# SOC_2_0.net
KiCad netlist of a schematic drawn in EAGLE
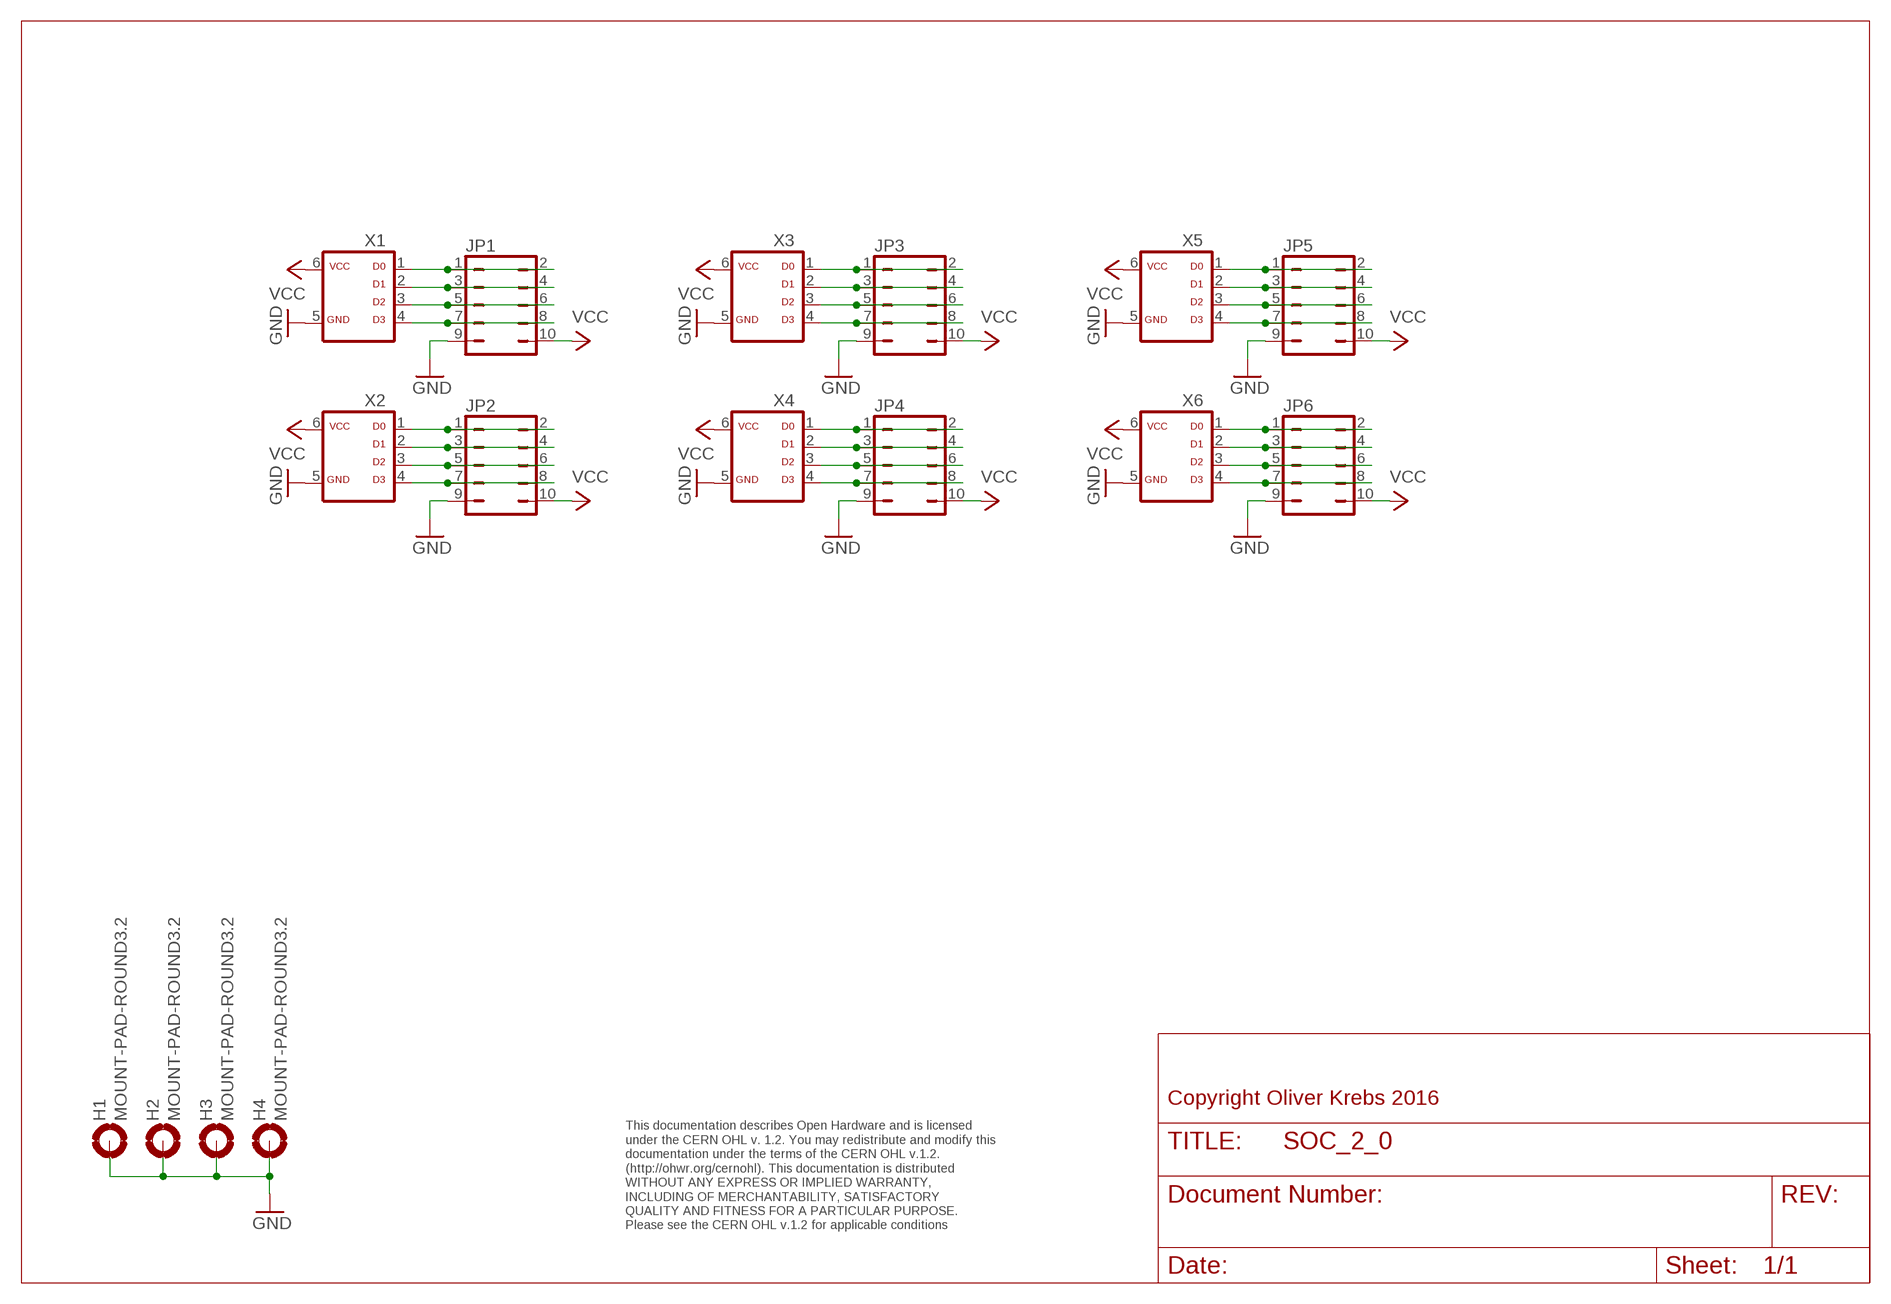
[diagram p0: schematic, sheet 1]

(export (version "E")
  (design (tool "Eeschema 10.0.6"))
  (components
    (comp (ref "H1")
      (value "MOUNT-PAD-ROUND3.2")
      (footprint "eagle-import:3,2-PAD")
      (libsource (lib "eagle-import") (part "MOUNT-PAD-ROUND3.2"))
    )
    (comp (ref "H2")
      (value "MOUNT-PAD-ROUND3.2")
      (footprint "eagle-import:3,2-PAD")
      (libsource (lib "eagle-import") (part "MOUNT-PAD-ROUND3.2"))
    )
    (comp (ref "H3")
      (value "MOUNT-PAD-ROUND3.2")
      (footprint "eagle-import:3,2-PAD")
      (libsource (lib "eagle-import") (part "MOUNT-PAD-ROUND3.2"))
    )
    (comp (ref "H4")
      (value "MOUNT-PAD-ROUND3.2")
      (footprint "eagle-import:3,2-PAD")
      (libsource (lib "eagle-import") (part "MOUNT-PAD-ROUND3.2"))
    )
    (comp (ref "JP1")
      (value "JP5Q")
      (footprint "eagle-import:JP5Q")
      (libsource (lib "eagle-import") (part "JP5Q"))
    )
    (comp (ref "JP2")
      (value "JP5Q")
      (footprint "eagle-import:JP5Q")
      (libsource (lib "eagle-import") (part "JP5Q"))
    )
    (comp (ref "JP3")
      (value "JP5Q")
      (footprint "eagle-import:JP5Q")
      (libsource (lib "eagle-import") (part "JP5Q"))
    )
    (comp (ref "JP4")
      (value "JP5Q")
      (footprint "eagle-import:JP5Q")
      (libsource (lib "eagle-import") (part "JP5Q"))
    )
    (comp (ref "JP5")
      (value "JP5Q")
      (footprint "eagle-import:JP5Q")
      (libsource (lib "eagle-import") (part "JP5Q"))
    )
    (comp (ref "JP6")
      (value "JP5Q")
      (footprint "eagle-import:JP5Q")
      (libsource (lib "eagle-import") (part "JP5Q"))
    )
    (comp (ref "X1")
      (value "ML6D")
      (footprint "eagle-import:ML-6")
      (libsource (lib "eagle-import") (part "ML6D"))
    )
    (comp (ref "X2")
      (value "ML6D")
      (footprint "eagle-import:ML-6")
      (libsource (lib "eagle-import") (part "ML6D"))
    )
    (comp (ref "X3")
      (value "ML6D")
      (footprint "eagle-import:ML-6")
      (libsource (lib "eagle-import") (part "ML6D"))
    )
    (comp (ref "X4")
      (value "ML6D")
      (footprint "eagle-import:ML-6")
      (libsource (lib "eagle-import") (part "ML6D"))
    )
    (comp (ref "X5")
      (value "ML6D")
      (footprint "eagle-import:ML-6")
      (libsource (lib "eagle-import") (part "ML6D"))
    )
    (comp (ref "X6")
      (value "ML6D")
      (footprint "eagle-import:ML-6")
      (libsource (lib "eagle-import") (part "ML6D"))
    )
  )
  (nets
    (net (code "1") (name "GND") (class "Default")
      (node (ref "H1") (pin "B3,2") (pinfunction "MOUNT_B3,2") (pintype "passive"))
      (node (ref "H2") (pin "B3,2") (pinfunction "MOUNT_B3,2") (pintype "passive"))
      (node (ref "H3") (pin "B3,2") (pinfunction "MOUNT_B3,2") (pintype "passive"))
      (node (ref "H4") (pin "B3,2") (pinfunction "MOUNT_B3,2") (pintype "passive"))
      (node (ref "JP1") (pin "9") (pinfunction "9_9") (pintype "passive"))
      (node (ref "JP2") (pin "9") (pinfunction "9_9") (pintype "passive"))
      (node (ref "JP3") (pin "9") (pinfunction "9_9") (pintype "passive"))
      (node (ref "JP4") (pin "9") (pinfunction "9_9") (pintype "passive"))
      (node (ref "JP5") (pin "9") (pinfunction "9_9") (pintype "passive"))
      (node (ref "JP6") (pin "9") (pinfunction "9_9") (pintype "passive"))
      (node (ref "X1") (pin "5") (pinfunction "5_5") (pintype "passive"))
      (node (ref "X2") (pin "5") (pinfunction "5_5") (pintype "passive"))
      (node (ref "X3") (pin "5") (pinfunction "5_5") (pintype "passive"))
      (node (ref "X4") (pin "5") (pinfunction "5_5") (pintype "passive"))
      (node (ref "X5") (pin "5") (pinfunction "5_5") (pintype "passive"))
      (node (ref "X6") (pin "5") (pinfunction "5_5") (pintype "passive"))
    )
    (net (code "2") (name "Net-(JP1-Pad1)") (class "Default")
      (node (ref "JP1") (pin "1") (pinfunction "1_1") (pintype "passive"))
      (node (ref "JP1") (pin "2") (pinfunction "2_2") (pintype "passive"))
      (node (ref "X1") (pin "1") (pinfunction "1_1") (pintype "passive"))
    )
    (net (code "3") (name "Net-(JP1-Pad3)") (class "Default")
      (node (ref "JP1") (pin "3") (pinfunction "3_3") (pintype "passive"))
      (node (ref "JP1") (pin "4") (pinfunction "4_4") (pintype "passive"))
      (node (ref "X1") (pin "2") (pinfunction "2_2") (pintype "passive"))
    )
    (net (code "4") (name "Net-(JP1-Pad5)") (class "Default")
      (node (ref "JP1") (pin "5") (pinfunction "5_5") (pintype "passive"))
      (node (ref "JP1") (pin "6") (pinfunction "6_6") (pintype "passive"))
      (node (ref "X1") (pin "3") (pinfunction "3_3") (pintype "passive"))
    )
    (net (code "5") (name "Net-(JP1-Pad7)") (class "Default")
      (node (ref "JP1") (pin "7") (pinfunction "7_7") (pintype "passive"))
      (node (ref "JP1") (pin "8") (pinfunction "8_8") (pintype "passive"))
      (node (ref "X1") (pin "4") (pinfunction "4_4") (pintype "passive"))
    )
    (net (code "6") (name "Net-(JP2-Pad1)") (class "Default")
      (node (ref "JP2") (pin "1") (pinfunction "1_1") (pintype "passive"))
      (node (ref "JP2") (pin "2") (pinfunction "2_2") (pintype "passive"))
      (node (ref "X2") (pin "1") (pinfunction "1_1") (pintype "passive"))
    )
    (net (code "7") (name "Net-(JP2-Pad3)") (class "Default")
      (node (ref "JP2") (pin "3") (pinfunction "3_3") (pintype "passive"))
      (node (ref "JP2") (pin "4") (pinfunction "4_4") (pintype "passive"))
      (node (ref "X2") (pin "2") (pinfunction "2_2") (pintype "passive"))
    )
    (net (code "8") (name "Net-(JP2-Pad5)") (class "Default")
      (node (ref "JP2") (pin "5") (pinfunction "5_5") (pintype "passive"))
      (node (ref "JP2") (pin "6") (pinfunction "6_6") (pintype "passive"))
      (node (ref "X2") (pin "3") (pinfunction "3_3") (pintype "passive"))
    )
    (net (code "9") (name "Net-(JP2-Pad7)") (class "Default")
      (node (ref "JP2") (pin "7") (pinfunction "7_7") (pintype "passive"))
      (node (ref "JP2") (pin "8") (pinfunction "8_8") (pintype "passive"))
      (node (ref "X2") (pin "4") (pinfunction "4_4") (pintype "passive"))
    )
    (net (code "10") (name "Net-(JP3-Pad1)") (class "Default")
      (node (ref "JP3") (pin "1") (pinfunction "1_1") (pintype "passive"))
      (node (ref "JP3") (pin "2") (pinfunction "2_2") (pintype "passive"))
      (node (ref "X3") (pin "1") (pinfunction "1_1") (pintype "passive"))
    )
    (net (code "11") (name "Net-(JP3-Pad3)") (class "Default")
      (node (ref "JP3") (pin "3") (pinfunction "3_3") (pintype "passive"))
      (node (ref "JP3") (pin "4") (pinfunction "4_4") (pintype "passive"))
      (node (ref "X3") (pin "2") (pinfunction "2_2") (pintype "passive"))
    )
    (net (code "12") (name "Net-(JP3-Pad5)") (class "Default")
      (node (ref "JP3") (pin "5") (pinfunction "5_5") (pintype "passive"))
      (node (ref "JP3") (pin "6") (pinfunction "6_6") (pintype "passive"))
      (node (ref "X3") (pin "3") (pinfunction "3_3") (pintype "passive"))
    )
    (net (code "13") (name "Net-(JP3-Pad7)") (class "Default")
      (node (ref "JP3") (pin "7") (pinfunction "7_7") (pintype "passive"))
      (node (ref "JP3") (pin "8") (pinfunction "8_8") (pintype "passive"))
      (node (ref "X3") (pin "4") (pinfunction "4_4") (pintype "passive"))
    )
    (net (code "14") (name "Net-(JP4-Pad1)") (class "Default")
      (node (ref "JP4") (pin "1") (pinfunction "1_1") (pintype "passive"))
      (node (ref "JP4") (pin "2") (pinfunction "2_2") (pintype "passive"))
      (node (ref "X4") (pin "1") (pinfunction "1_1") (pintype "passive"))
    )
    (net (code "15") (name "Net-(JP4-Pad3)") (class "Default")
      (node (ref "JP4") (pin "3") (pinfunction "3_3") (pintype "passive"))
      (node (ref "JP4") (pin "4") (pinfunction "4_4") (pintype "passive"))
      (node (ref "X4") (pin "2") (pinfunction "2_2") (pintype "passive"))
    )
    (net (code "16") (name "Net-(JP4-Pad5)") (class "Default")
      (node (ref "JP4") (pin "5") (pinfunction "5_5") (pintype "passive"))
      (node (ref "JP4") (pin "6") (pinfunction "6_6") (pintype "passive"))
      (node (ref "X4") (pin "3") (pinfunction "3_3") (pintype "passive"))
    )
    (net (code "17") (name "Net-(JP4-Pad7)") (class "Default")
      (node (ref "JP4") (pin "7") (pinfunction "7_7") (pintype "passive"))
      (node (ref "JP4") (pin "8") (pinfunction "8_8") (pintype "passive"))
      (node (ref "X4") (pin "4") (pinfunction "4_4") (pintype "passive"))
    )
    (net (code "18") (name "Net-(JP5-Pad1)") (class "Default")
      (node (ref "JP5") (pin "1") (pinfunction "1_1") (pintype "passive"))
      (node (ref "JP5") (pin "2") (pinfunction "2_2") (pintype "passive"))
      (node (ref "X5") (pin "1") (pinfunction "1_1") (pintype "passive"))
    )
    (net (code "19") (name "Net-(JP5-Pad3)") (class "Default")
      (node (ref "JP5") (pin "3") (pinfunction "3_3") (pintype "passive"))
      (node (ref "JP5") (pin "4") (pinfunction "4_4") (pintype "passive"))
      (node (ref "X5") (pin "2") (pinfunction "2_2") (pintype "passive"))
    )
    (net (code "20") (name "Net-(JP5-Pad5)") (class "Default")
      (node (ref "JP5") (pin "5") (pinfunction "5_5") (pintype "passive"))
      (node (ref "JP5") (pin "6") (pinfunction "6_6") (pintype "passive"))
      (node (ref "X5") (pin "3") (pinfunction "3_3") (pintype "passive"))
    )
    (net (code "21") (name "Net-(JP5-Pad7)") (class "Default")
      (node (ref "JP5") (pin "7") (pinfunction "7_7") (pintype "passive"))
      (node (ref "JP5") (pin "8") (pinfunction "8_8") (pintype "passive"))
      (node (ref "X5") (pin "4") (pinfunction "4_4") (pintype "passive"))
    )
    (net (code "22") (name "Net-(JP6-Pad1)") (class "Default")
      (node (ref "JP6") (pin "1") (pinfunction "1_1") (pintype "passive"))
      (node (ref "JP6") (pin "2") (pinfunction "2_2") (pintype "passive"))
      (node (ref "X6") (pin "1") (pinfunction "1_1") (pintype "passive"))
    )
    (net (code "23") (name "Net-(JP6-Pad3)") (class "Default")
      (node (ref "JP6") (pin "3") (pinfunction "3_3") (pintype "passive"))
      (node (ref "JP6") (pin "4") (pinfunction "4_4") (pintype "passive"))
      (node (ref "X6") (pin "2") (pinfunction "2_2") (pintype "passive"))
    )
    (net (code "24") (name "Net-(JP6-Pad5)") (class "Default")
      (node (ref "JP6") (pin "5") (pinfunction "5_5") (pintype "passive"))
      (node (ref "JP6") (pin "6") (pinfunction "6_6") (pintype "passive"))
      (node (ref "X6") (pin "3") (pinfunction "3_3") (pintype "passive"))
    )
    (net (code "25") (name "Net-(JP6-Pad7)") (class "Default")
      (node (ref "JP6") (pin "7") (pinfunction "7_7") (pintype "passive"))
      (node (ref "JP6") (pin "8") (pinfunction "8_8") (pintype "passive"))
      (node (ref "X6") (pin "4") (pinfunction "4_4") (pintype "passive"))
    )
    (net (code "26") (name "VCC") (class "Default")
      (node (ref "JP1") (pin "10") (pinfunction "10_10") (pintype "passive"))
      (node (ref "JP2") (pin "10") (pinfunction "10_10") (pintype "passive"))
      (node (ref "JP3") (pin "10") (pinfunction "10_10") (pintype "passive"))
      (node (ref "JP4") (pin "10") (pinfunction "10_10") (pintype "passive"))
      (node (ref "JP5") (pin "10") (pinfunction "10_10") (pintype "passive"))
      (node (ref "JP6") (pin "10") (pinfunction "10_10") (pintype "passive"))
      (node (ref "X1") (pin "6") (pinfunction "6_6") (pintype "passive"))
      (node (ref "X2") (pin "6") (pinfunction "6_6") (pintype "passive"))
      (node (ref "X3") (pin "6") (pinfunction "6_6") (pintype "passive"))
      (node (ref "X4") (pin "6") (pinfunction "6_6") (pintype "passive"))
      (node (ref "X5") (pin "6") (pinfunction "6_6") (pintype "passive"))
      (node (ref "X6") (pin "6") (pinfunction "6_6") (pintype "passive"))
    )
  )
)
